# 8_PCIE.net
KiCad netlist of a schematic drawn in Altium Designer
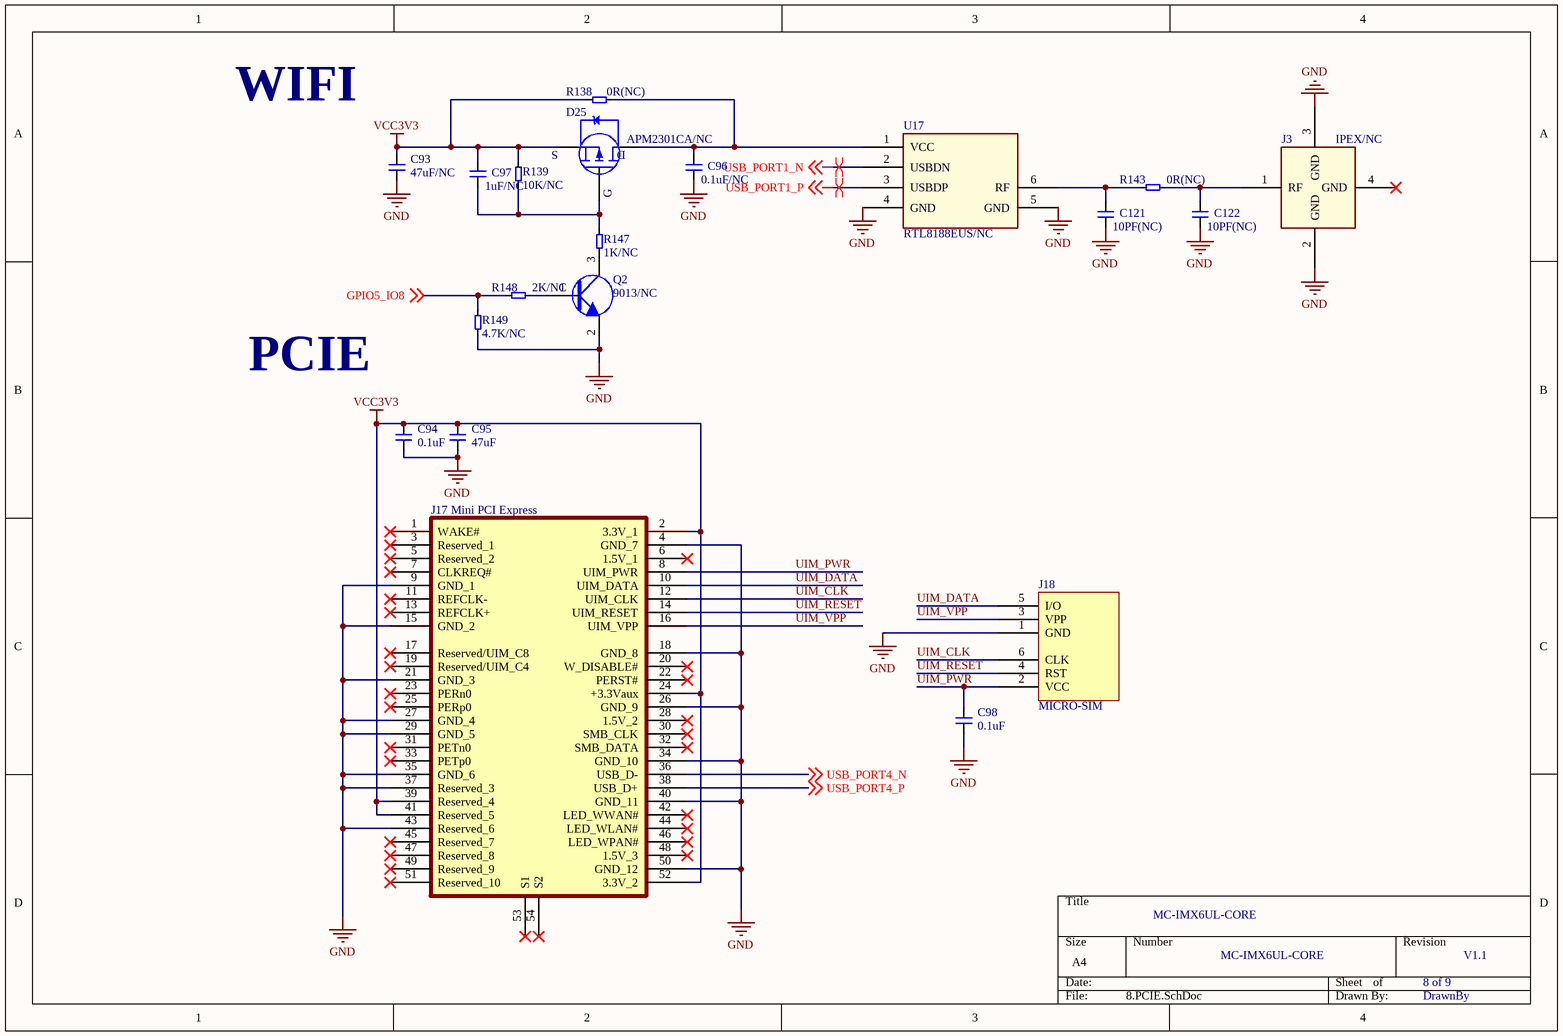
[diagram p0: 8.PCIE.SchDoc]

(export (version "E")
  (design (tool "Eeschema 10.0.6"))
  (components
    (comp (ref "C93")
      (value "47uF/NC")
      (footprint "1206C")
      (description "电容")
      (libsource (lib "LDT-SCH") (part "电容"))
    )
    (comp (ref "C94")
      (value "0.1uF")
      (footprint "0603C")
      (description "电容")
      (libsource (lib "LDT-SCH") (part "电容"))
    )
    (comp (ref "C95")
      (value "47uF")
      (footprint "1206C")
      (description "电容")
      (libsource (lib "LDT-SCH") (part "电容"))
    )
    (comp (ref "C96")
      (value "0.1uF/NC")
      (footprint "0603C")
      (description "电容")
      (libsource (lib "LDT-SCH") (part "电容"))
    )
    (comp (ref "C97")
      (value "1uF/NC")
      (footprint "0603C")
      (description "电容")
      (libsource (lib "LDT-SCH") (part "电容"))
    )
    (comp (ref "C98")
      (value "0.1uF")
      (footprint "0603C")
      (description "电容")
      (libsource (lib "LDT-SCH") (part "电容"))
    )
    (comp (ref "C121")
      (value "10PF(NC)")
      (footprint "0402C")
      (description "电容")
      (libsource (lib "LDT-SCH") (part "电容"))
    )
    (comp (ref "C122")
      (value "10PF(NC)")
      (footprint "0402C")
      (description "电容")
      (libsource (lib "LDT-SCH") (part "电容"))
    )
    (comp (ref "D25")
      (value "APM2301CA/NC")
      (footprint "SOT-23")
      (libsource (lib "LDT-SCH") (part "APM2301CA"))
    )
    (comp (ref "J3") (value "IPEX/NC") (footprint "IPEX") (libsource (lib "LDT-SCH") (part "IPEX")))
    (comp (ref "J17")
      (value "Mini PCI Express")
      (footprint "MINI-PCIE")
      (description "MPC24-52K3311")
      (libsource (lib "LDT-SCH") (part "MINIPCIE"))
    )
    (comp (ref "J18")
      (value "MICRO-SIM")
      (footprint "MACRO-SIM")
      (libsource (lib "LDT-SCH") (part "MICRO-SIM"))
    )
    (comp (ref "Q2") (value "9013/NC") (footprint "SOT-23") (libsource (lib "LDT-SCH") (part "9013")))
    (comp (ref "R138")
      (value "0R(NC)")
      (footprint "0603R")
      (description "电阻")
      (libsource (lib "*") (part "电阻"))
    )
    (comp (ref "R139")
      (value "10K/NC")
      (footprint "0603R")
      (description "电阻")
      (libsource (lib "*") (part "电阻"))
    )
    (comp (ref "R143")
      (value "0R(NC)")
      (footprint "0402R")
      (description "电阻")
      (libsource (lib "*") (part "电阻"))
    )
    (comp (ref "R147")
      (value "1K/NC")
      (footprint "0603R")
      (description "电阻")
      (libsource (lib "*") (part "电阻"))
    )
    (comp (ref "R148")
      (value "2K/NC")
      (footprint "0603R")
      (description "电阻")
      (libsource (lib "*") (part "电阻"))
    )
    (comp (ref "R149")
      (value "4.7K/NC")
      (footprint "0603R")
      (description "电阻")
      (libsource (lib "*") (part "电阻"))
    )
    (comp (ref "U17")
      (value "RTL8188EUS/NC")
      (footprint "RTL8188EUS 13*12.2")
      (libsource (lib "LDT-SCH") (part "RTL8188EUS-13*12.2"))
    )
  )
  (nets
    (net (code "1") (name "/UIM_CLK") (class "Default")
      (node (ref "J17") (pin "12") (pinfunction "UIM_CLK_12") (pintype "passive"))
      (node (ref "J18") (pin "6") (pinfunction "CLK_6") (pintype "passive"))
    )
    (net (code "2") (name "/UIM_DATA") (class "Default")
      (node (ref "J17") (pin "10") (pinfunction "UIM_DATA_10") (pintype "passive"))
      (node (ref "J18") (pin "5") (pinfunction "I/O_5") (pintype "passive"))
    )
    (net (code "3") (name "/UIM_PWR") (class "Default")
      (node (ref "C98") (pin "1") (pintype "passive"))
      (node (ref "J17") (pin "8") (pinfunction "UIM_PWR_8") (pintype "passive"))
      (node (ref "J18") (pin "2") (pinfunction "VCC_2") (pintype "passive"))
    )
    (net (code "4") (name "/UIM_RESET") (class "Default")
      (node (ref "J17") (pin "14") (pinfunction "UIM_RESET_14") (pintype "passive"))
      (node (ref "J18") (pin "4") (pinfunction "RST_4") (pintype "passive"))
    )
    (net (code "5") (name "/UIM_VPP") (class "Default")
      (node (ref "J17") (pin "16") (pinfunction "UIM_VPP_16") (pintype "passive"))
      (node (ref "J18") (pin "3") (pinfunction "VPP_3") (pintype "passive"))
    )
    (net (code "6") (name "GND") (class "Default")
      (node (ref "C121") (pin "2") (pintype "passive"))
      (node (ref "C122") (pin "2") (pintype "passive"))
      (node (ref "C93") (pin "2") (pintype "passive"))
      (node (ref "C94") (pin "2") (pintype "passive"))
      (node (ref "C95") (pin "2") (pintype "passive"))
      (node (ref "C96") (pin "2") (pintype "passive"))
      (node (ref "C98") (pin "2") (pintype "passive"))
      (node (ref "J17") (pin "15") (pinfunction "GND_2_15") (pintype "passive"))
      (node (ref "J17") (pin "18") (pinfunction "GND_8_18") (pintype "passive"))
      (node (ref "J17") (pin "21") (pinfunction "GND_3_21") (pintype "passive"))
      (node (ref "J17") (pin "26") (pinfunction "GND_9_26") (pintype "passive"))
      (node (ref "J17") (pin "27") (pinfunction "GND_4_27") (pintype "passive"))
      (node (ref "J17") (pin "29") (pinfunction "GND_5_29") (pintype "passive"))
      (node (ref "J17") (pin "34") (pinfunction "GND_10_34") (pintype "passive"))
      (node (ref "J17") (pin "35") (pinfunction "GND_6_35") (pintype "passive"))
      (node (ref "J17") (pin "37") (pinfunction "Reserved_3_37") (pintype "passive"))
      (node (ref "J17") (pin "4") (pinfunction "GND_7_4") (pintype "passive"))
      (node (ref "J17") (pin "40") (pinfunction "GND_11_40") (pintype "passive"))
      (node (ref "J17") (pin "43") (pinfunction "Reserved_6_43") (pintype "passive"))
      (node (ref "J17") (pin "50") (pinfunction "GND_12_50") (pintype "passive"))
      (node (ref "J17") (pin "9") (pinfunction "GND_1_9") (pintype "passive"))
      (node (ref "J18") (pin "1") (pinfunction "GND_1") (pintype "passive"))
      (node (ref "J3") (pin "2") (pinfunction "GND_2") (pintype "passive"))
      (node (ref "J3") (pin "3") (pinfunction "GND_3") (pintype "passive"))
      (node (ref "Q2") (pin "2") (pintype "passive"))
      (node (ref "R149") (pin "2") (pintype "passive"))
      (node (ref "U17") (pin "4") (pinfunction "GND_4") (pintype "passive"))
      (node (ref "U17") (pin "5") (pinfunction "GND_5") (pintype "passive"))
    )
    (net (code "7") (name "GPIO5_IO8") (class "Default")
      (node (ref "R148") (pin "1") (pintype "passive"))
      (node (ref "R149") (pin "1") (pintype "passive"))
    )
    (net (code "8") (name "Net-(C97-Pad2)") (class "Default")
      (node (ref "C97") (pin "2") (pintype "passive"))
      (node (ref "D25") (pin "1") (pintype "passive"))
      (node (ref "R139") (pin "1") (pintype "passive"))
      (node (ref "R147") (pin "2") (pintype "passive"))
    )
    (net (code "9") (name "Net-(J3-RF)") (class "Default")
      (node (ref "C122") (pin "1") (pintype "passive"))
      (node (ref "J3") (pin "1") (pinfunction "RF_1") (pintype "passive"))
      (node (ref "R143") (pin "2") (pintype "passive"))
    )
    (net (code "10") (name "Net-(Q2-Pad1)") (class "Default")
      (node (ref "Q2") (pin "1") (pintype "passive"))
      (node (ref "R148") (pin "2") (pintype "passive"))
    )
    (net (code "11") (name "Net-(Q2-Pad3)") (class "Default")
      (node (ref "Q2") (pin "3") (pintype "passive"))
      (node (ref "R147") (pin "1") (pintype "passive"))
    )
    (net (code "12") (name "Net-(U17-RF)") (class "Default")
      (node (ref "C121") (pin "1") (pintype "passive"))
      (node (ref "R143") (pin "1") (pintype "passive"))
      (node (ref "U17") (pin "6") (pinfunction "RF_6") (pintype "passive"))
    )
    (net (code "13") (name "Net-(U17-VCC)") (class "Default")
      (node (ref "C96") (pin "1") (pintype "passive"))
      (node (ref "D25") (pin "3") (pintype "passive"))
      (node (ref "R138") (pin "1") (pintype "passive"))
      (node (ref "U17") (pin "1") (pinfunction "VCC_1") (pintype "passive"))
    )
    (net (code "14") (name "USB_PORT1_N") (class "Default")
      (node (ref "U17") (pin "2") (pinfunction "USBDN_2") (pintype "passive"))
    )
    (net (code "15") (name "USB_PORT1_P") (class "Default")
      (node (ref "U17") (pin "3") (pinfunction "USBDP_3") (pintype "passive"))
    )
    (net (code "16") (name "USB_PORT4_N") (class "Default")
      (node (ref "J17") (pin "36") (pinfunction "USB_D-_36") (pintype "passive"))
    )
    (net (code "17") (name "USB_PORT4_P") (class "Default")
      (node (ref "J17") (pin "38") (pinfunction "USB_D+_38") (pintype "passive"))
    )
    (net (code "18") (name "VCC3V3") (class "Default")
      (node (ref "C93") (pin "1") (pintype "passive"))
      (node (ref "C94") (pin "1") (pintype "passive"))
      (node (ref "C95") (pin "1") (pintype "passive"))
      (node (ref "C97") (pin "1") (pintype "passive"))
      (node (ref "D25") (pin "2") (pintype "passive"))
      (node (ref "J17") (pin "2") (pinfunction "3.3V_1_2") (pintype "passive"))
      (node (ref "J17") (pin "24") (pinfunction "+3.3Vaux_24") (pintype "passive"))
      (node (ref "J17") (pin "39") (pinfunction "Reserved_4_39") (pintype "passive"))
      (node (ref "J17") (pin "41") (pinfunction "Reserved_5_41") (pintype "passive"))
      (node (ref "J17") (pin "52") (pinfunction "3.3V_2_52") (pintype "passive"))
      (node (ref "R138") (pin "2") (pintype "passive"))
      (node (ref "R139") (pin "2") (pintype "passive"))
    )
    (net (code "19") (name "unconnected-(J3-GND-Pad4)") (class "Default")
      (node (ref "J3") (pin "4") (pinfunction "GND_4") (pintype "passive+no_connect"))
    )
    (net (code "20") (name "unconnected-(J17-1.5V_1-Pad6)") (class "Default")
      (node (ref "J17") (pin "6") (pinfunction "1.5V_1_6") (pintype "passive+no_connect"))
    )
    (net (code "21") (name "unconnected-(J17-1.5V_2-Pad28)") (class "Default")
      (node (ref "J17") (pin "28") (pinfunction "1.5V_2_28") (pintype "passive+no_connect"))
    )
    (net (code "22") (name "unconnected-(J17-1.5V_3-Pad48)") (class "Default")
      (node (ref "J17") (pin "48") (pinfunction "1.5V_3_48") (pintype "passive+no_connect"))
    )
    (net (code "23") (name "unconnected-(J17-CLKREQ#-Pad7)") (class "Default")
      (node (ref "J17") (pin "7") (pinfunction "CLKREQ#_7") (pintype "passive+no_connect"))
    )
    (net (code "24") (name "unconnected-(J17-LED_WLAN#-Pad44)") (class "Default")
      (node (ref "J17") (pin "44") (pinfunction "LED_WLAN#_44") (pintype "passive+no_connect"))
    )
    (net (code "25") (name "unconnected-(J17-LED_WPAN#-Pad46)") (class "Default")
      (node (ref "J17") (pin "46") (pinfunction "LED_WPAN#_46") (pintype "passive+no_connect"))
    )
    (net (code "26") (name "unconnected-(J17-LED_WWAN#-Pad42)") (class "Default")
      (node (ref "J17") (pin "42") (pinfunction "LED_WWAN#_42") (pintype "passive+no_connect"))
    )
    (net (code "27") (name "unconnected-(J17-PERST#-Pad22)") (class "Default")
      (node (ref "J17") (pin "22") (pinfunction "PERST#_22") (pintype "passive+no_connect"))
    )
    (net (code "28") (name "unconnected-(J17-PERn0-Pad23)") (class "Default")
      (node (ref "J17") (pin "23") (pinfunction "PERn0_23") (pintype "passive+no_connect"))
    )
    (net (code "29") (name "unconnected-(J17-PERp0-Pad25)") (class "Default")
      (node (ref "J17") (pin "25") (pinfunction "PERp0_25") (pintype "passive+no_connect"))
    )
    (net (code "30") (name "unconnected-(J17-PETn0-Pad31)") (class "Default")
      (node (ref "J17") (pin "31") (pinfunction "PETn0_31") (pintype "passive+no_connect"))
    )
    (net (code "31") (name "unconnected-(J17-PETp0-Pad33)") (class "Default")
      (node (ref "J17") (pin "33") (pinfunction "PETp0_33") (pintype "passive+no_connect"))
    )
    (net (code "32") (name "unconnected-(J17-REFCLK+-Pad13)") (class "Default")
      (node (ref "J17") (pin "13") (pinfunction "REFCLK+_13") (pintype "passive+no_connect"))
    )
    (net (code "33") (name "unconnected-(J17-REFCLK--Pad11)") (class "Default")
      (node (ref "J17") (pin "11") (pinfunction "REFCLK-_11") (pintype "passive+no_connect"))
    )
    (net (code "34") (name "unconnected-(J17-Reserved_1-Pad3)") (class "Default")
      (node (ref "J17") (pin "3") (pinfunction "Reserved_1_3") (pintype "passive+no_connect"))
    )
    (net (code "35") (name "unconnected-(J17-Reserved_2-Pad5)") (class "Default")
      (node (ref "J17") (pin "5") (pinfunction "Reserved_2_5") (pintype "passive+no_connect"))
    )
    (net (code "36") (name "unconnected-(J17-Reserved_7-Pad45)") (class "Default")
      (node (ref "J17") (pin "45") (pinfunction "Reserved_7_45") (pintype "passive+no_connect"))
    )
    (net (code "37") (name "unconnected-(J17-Reserved_8-Pad47)") (class "Default")
      (node (ref "J17") (pin "47") (pinfunction "Reserved_8_47") (pintype "passive+no_connect"))
    )
    (net (code "38") (name "unconnected-(J17-Reserved_9-Pad49)") (class "Default")
      (node (ref "J17") (pin "49") (pinfunction "Reserved_9_49") (pintype "passive+no_connect"))
    )
    (net (code "39") (name "unconnected-(J17-Reserved_10-Pad51)") (class "Default")
      (node (ref "J17") (pin "51") (pinfunction "Reserved_10_51") (pintype "passive+no_connect"))
    )
    (net (code "40") (name "unconnected-(J17-Reserved{slash}UIM_C4-Pad19)") (class "Default")
      (node (ref "J17") (pin "19") (pinfunction "Reserved/UIM_C4_19") (pintype "passive+no_connect"))
    )
    (net (code "41") (name "unconnected-(J17-Reserved{slash}UIM_C8-Pad17)") (class "Default")
      (node (ref "J17") (pin "17") (pinfunction "Reserved/UIM_C8_17") (pintype "passive+no_connect"))
    )
    (net (code "42") (name "unconnected-(J17-S1-Pad53)") (class "Default")
      (node (ref "J17") (pin "53") (pinfunction "S1_53") (pintype "passive+no_connect"))
    )
    (net (code "43") (name "unconnected-(J17-S2-Pad54)") (class "Default")
      (node (ref "J17") (pin "54") (pinfunction "S2_54") (pintype "passive+no_connect"))
    )
    (net (code "44") (name "unconnected-(J17-SMB_CLK-Pad30)") (class "Default")
      (node (ref "J17") (pin "30") (pinfunction "SMB_CLK_30") (pintype "passive+no_connect"))
    )
    (net (code "45") (name "unconnected-(J17-SMB_DATA-Pad32)") (class "Default")
      (node (ref "J17") (pin "32") (pinfunction "SMB_DATA_32") (pintype "passive+no_connect"))
    )
    (net (code "46") (name "unconnected-(J17-WAKE#-Pad1)") (class "Default")
      (node (ref "J17") (pin "1") (pinfunction "WAKE#_1") (pintype "passive+no_connect"))
    )
    (net (code "47") (name "unconnected-(J17-W_DISABLE#-Pad20)") (class "Default")
      (node (ref "J17") (pin "20") (pinfunction "W_DISABLE#_20") (pintype "passive+no_connect"))
    )
  )
)
